# Chanel.net
KiCad netlist of a schematic drawn in Altium Designer
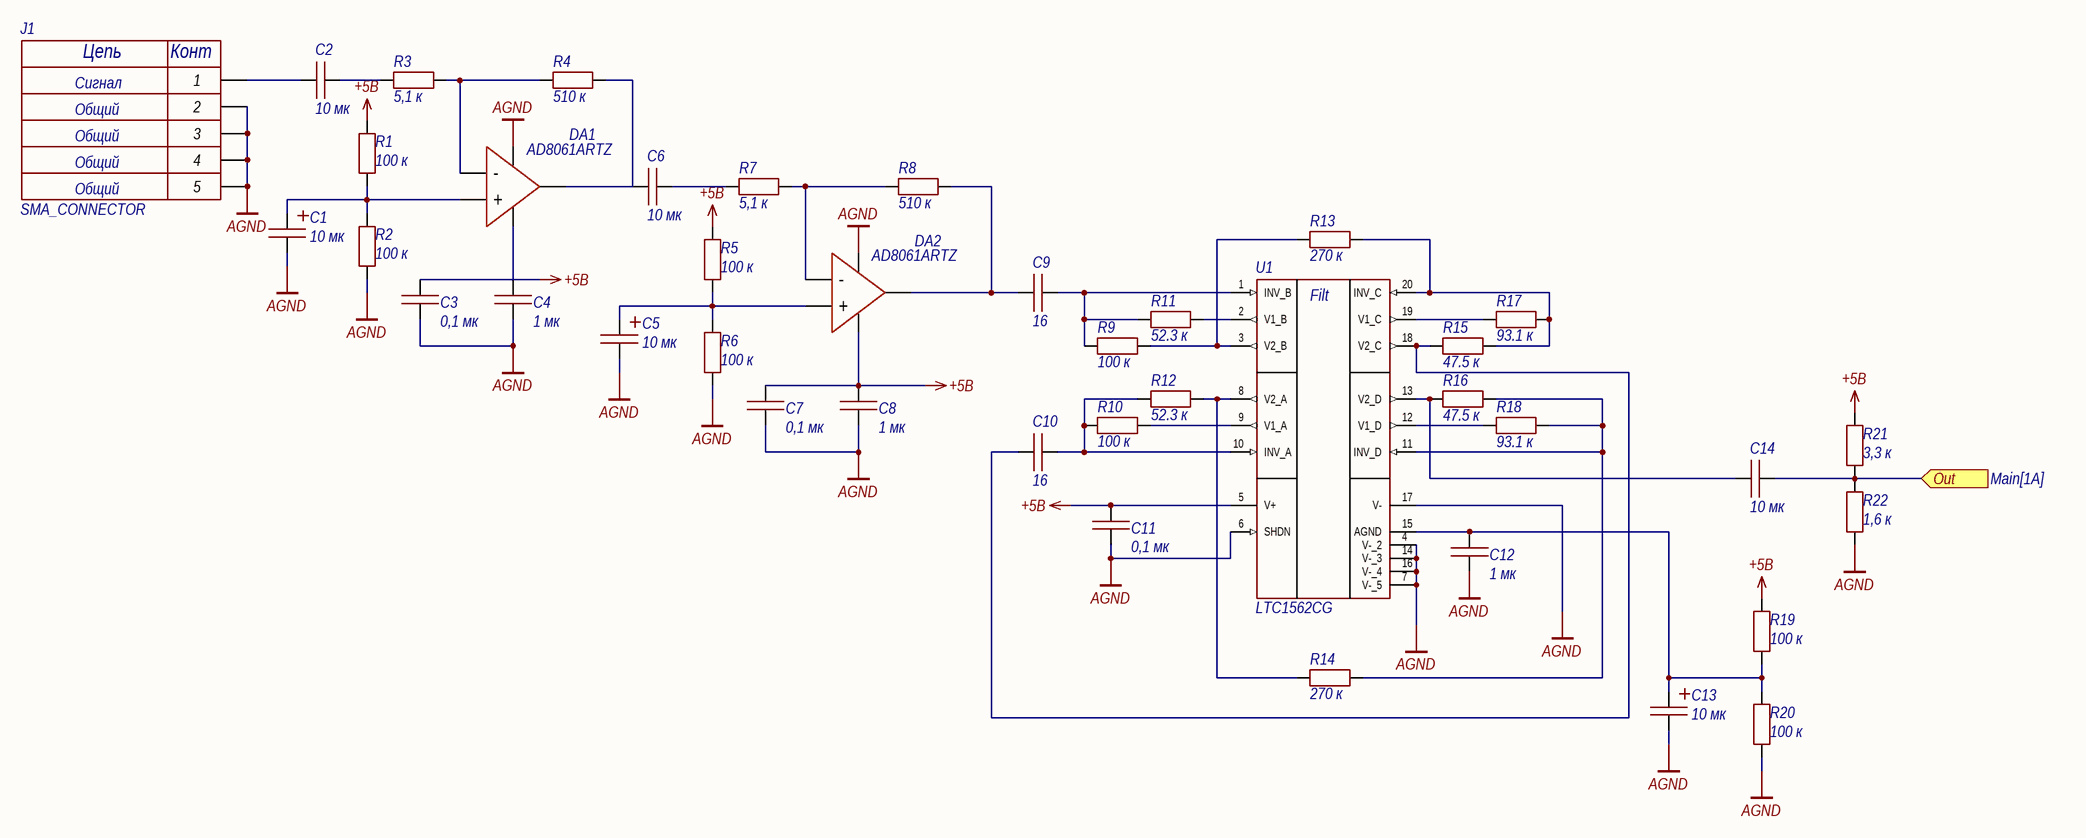
[diagram p0: Chanel.SchDoc]

(export (version "E")
  (design (tool "Eeschema 10.0.6"))
  (components
    (comp (ref "C1")
      (value "10 мк")
      (footprint "TC_A")
      (description "Танталовый конденсатор")
      (fields (field (name "PART NUMBER") "Capacitor_10u_10_50V_TC_A") (field (name "TOLERANCE") "0,1"))
      (libsource (lib "Hydrolib") (part "Capacitor_polar"))
    )
    (comp (ref "C2")
      (value "10 мк")
      (footprint "1210C")
      (description "Конденсатор 1210C ёмкостью 10 мк 10%, 35 В, X7R")
      (fields (field (name "PART NUMBER") "Capacitor_10u_10_35V_X7R_1210C") (field (name "TOLERANCE") "10%"))
      (libsource (lib "Hydrolib") (part "Capacitor"))
    )
    (comp (ref "C3")
      (value "0,1 мк")
      (footprint "0603C")
      (description "Конденсатор 0603C ёмкостью 0,1 мк 10%, 50 В, X7R")
      (fields (field (name "PART NUMBER") "Capacitor_0,1u_10_50V_X7R_0603C") (field (name "TOLERANCE") "10%"))
      (libsource (lib "Hydrolib") (part "Capacitor"))
    )
    (comp (ref "C4")
      (value "1 мк")
      (footprint "0603C")
      (description "Конденсатор 0603C ёмкостью 1 мк 10%, 50 В, X7R")
      (fields (field (name "PART NUMBER") "Capacitor_1u_10_50V_X7R_0603C") (field (name "TOLERANCE") "10%"))
      (libsource (lib "Hydrolib") (part "Capacitor"))
    )
    (comp (ref "C5")
      (value "10 мк")
      (footprint "TC_A")
      (description "Танталовый конденсатор")
      (fields (field (name "PART NUMBER") "Capacitor_10u_10_50V_TC_A") (field (name "TOLERANCE") "0,1"))
      (libsource (lib "Hydrolib") (part "Capacitor_polar"))
    )
    (comp (ref "C6")
      (value "10 мк")
      (footprint "1210C")
      (description "Конденсатор 1210C ёмкостью 10 мк 10%, 35 В, X7R")
      (fields (field (name "PART NUMBER") "Capacitor_10u_10_35V_X7R_1210C") (field (name "TOLERANCE") "10%"))
      (libsource (lib "Hydrolib") (part "Capacitor"))
    )
    (comp (ref "C7")
      (value "0,1 мк")
      (footprint "0603C")
      (description "Конденсатор 0603C ёмкостью 0,1 мк 10%, 50 В, X7R")
      (fields (field (name "PART NUMBER") "Capacitor_0,1u_10_50V_X7R_0603C") (field (name "TOLERANCE") "10%"))
      (libsource (lib "Hydrolib") (part "Capacitor"))
    )
    (comp (ref "C8")
      (value "1 мк")
      (footprint "0603C")
      (description "Конденсатор 0603C ёмкостью 1 мк 10%, 50 В, X7R")
      (fields (field (name "PART NUMBER") "Capacitor_1u_10_50V_X7R_0603C") (field (name "TOLERANCE") "10%"))
      (libsource (lib "Hydrolib") (part "Capacitor"))
    )
    (comp (ref "C9")
      (value "16")
      (footprint "0603C")
      (description "Конденсатор 0603C ёмкостью 1 н 10%, 50 В, X7R")
      (fields (field (name "PART NUMBER") "Capacitor_1n_10_50V_X7R_0603C") (field (name "TOLERANCE") "10%"))
      (libsource (lib "Hydrolib") (part "Capacitor"))
    )
    (comp (ref "C10")
      (value "16")
      (footprint "0603C")
      (description "Конденсатор 0603C ёмкостью 1 н 10%, 50 В, X7R")
      (fields (field (name "PART NUMBER") "Capacitor_1n_10_50V_X7R_0603C") (field (name "TOLERANCE") "10%"))
      (libsource (lib "Hydrolib") (part "Capacitor"))
    )
    (comp (ref "C11")
      (value "0,1 мк")
      (footprint "0603C")
      (description "Конденсатор 0603C ёмкостью 0,1 мк 10%, 50 В, X7R")
      (fields (field (name "PART NUMBER") "Capacitor_0,1u_10_50V_X7R_0603C") (field (name "TOLERANCE") "10%"))
      (libsource (lib "Hydrolib") (part "Capacitor"))
    )
    (comp (ref "C12")
      (value "1 мк")
      (footprint "0603C")
      (description "Конденсатор 0603C ёмкостью 1 мк 10%, 50 В, X7R")
      (fields (field (name "PART NUMBER") "Capacitor_1u_10_50V_X7R_0603C") (field (name "TOLERANCE") "10%"))
      (libsource (lib "Hydrolib") (part "Capacitor"))
    )
    (comp (ref "C13")
      (value "10 мк")
      (footprint "TC_A")
      (description "Танталовый конденсатор")
      (fields (field (name "PART NUMBER") "Capacitor_10u_10_50V_TC_A") (field (name "TOLERANCE") "0,1"))
      (libsource (lib "Hydrolib") (part "Capacitor_polar"))
    )
    (comp (ref "C14")
      (value "10 мк")
      (footprint "0603C")
      (description "Конденсатор 0603C ёмкостью 0,1 мк 10%, 50 В, X7R")
      (fields (field (name "PART NUMBER") "Capacitor_0,1u_10_50V_X7R_0603C") (field (name "TOLERANCE") "10%"))
      (libsource (lib "Hydrolib") (part "Capacitor"))
    )
    (comp (ref "DA1")
      (value "AD8061ARTZ")
      (footprint "SOT23-5")
      (description "Операционный усилитель Rail-to-Rail, 1-канальный")
      (fields (field (name "PART NUMBER") "TS951ILT") (field (name "АВТОР") "glebmih"))
      (libsource (lib "Hydrolib") (part "TS951ILT"))
    )
    (comp (ref "DA2")
      (value "AD8061ARTZ")
      (footprint "SOT23-5")
      (description "Операционный усилитель Rail-to-Rail, 1-канальный")
      (fields (field (name "PART NUMBER") "TS951ILT") (field (name "АВТОР") "glebmih"))
      (libsource (lib "Hydrolib") (part "TS951ILT"))
    )
    (comp (ref "J1")
      (value "SMA_CONNECTOR")
      (footprint "SMA_CONNECTOR")
      (description "Straight SMA Connector")
      (fields (field (name "MP") "altium_native_batch"))
      (libsource (lib "Hydrolib") (part "SMA_CONNECTOR"))
    )
    (comp (ref "R1")
      (value "100 к")
      (footprint "0603R")
      (description "Резистор номиналом 100 кОм 1%")
      (fields (field (name "PART NUMBER") "Resistor_100k_1_0603") (field (name "TOLERANCE") "1%"))
      (libsource (lib "Hydrolib") (part "Resistor"))
    )
    (comp (ref "R2")
      (value "100 к")
      (footprint "0603R")
      (description "Резистор номиналом 100 кОм 1%")
      (fields (field (name "PART NUMBER") "Resistor_100k_1_0603") (field (name "TOLERANCE") "1%"))
      (libsource (lib "Hydrolib") (part "Resistor"))
    )
    (comp (ref "R3")
      (value "5,1 к")
      (footprint "0603R")
      (description "Резистор номиналом 100 кОм 1%")
      (fields (field (name "PART NUMBER") "Resistor_100k_1_0603") (field (name "TOLERANCE") "1%"))
      (libsource (lib "") (part "Resistor_2"))
    )
    (comp (ref "R4")
      (value "510 к")
      (footprint "0603R")
      (description "Резистор номиналом 510 кОм 1%")
      (fields (field (name "PART NUMBER") "Resistor_510k_1_0603") (field (name "TOLERANCE") "1%"))
      (libsource (lib "") (part "Resistor_1"))
    )
    (comp (ref "R5")
      (value "100 к")
      (footprint "0603R")
      (description "Резистор номиналом 100 кОм 1%")
      (fields (field (name "PART NUMBER") "Resistor_100k_1_0603") (field (name "TOLERANCE") "1%"))
      (libsource (lib "Hydrolib") (part "Resistor"))
    )
    (comp (ref "R6")
      (value "100 к")
      (footprint "0603R")
      (description "Резистор номиналом 100 кОм 1%")
      (fields (field (name "PART NUMBER") "Resistor_100k_1_0603") (field (name "TOLERANCE") "1%"))
      (libsource (lib "Hydrolib") (part "Resistor"))
    )
    (comp (ref "R7")
      (value "5,1 к")
      (footprint "0603R")
      (description "Резистор номиналом 100 кОм 1%")
      (fields (field (name "PART NUMBER") "Resistor_100k_1_0603") (field (name "TOLERANCE") "1%"))
      (libsource (lib "") (part "Resistor_2"))
    )
    (comp (ref "R8")
      (value "510 к")
      (footprint "0603R")
      (description "Резистор номиналом 510 кОм 1%")
      (fields (field (name "PART NUMBER") "Resistor_510k_1_0603") (field (name "TOLERANCE") "1%"))
      (libsource (lib "") (part "Resistor_1"))
    )
    (comp (ref "R9")
      (value "100 к")
      (footprint "0603R")
      (description "Резистор номиналом 51 кОм 1%")
      (fields (field (name "PART NUMBER") "Resistor_51k_1_0603") (field (name "TOLERANCE") "1%"))
      (libsource (lib "") (part "Resistor_1"))
    )
    (comp (ref "R10")
      (value "100 к")
      (footprint "0603R")
      (description "Резистор номиналом 51 кОм 1%")
      (fields (field (name "PART NUMBER") "Resistor_51k_1_0603") (field (name "TOLERANCE") "1%"))
      (libsource (lib "") (part "Resistor_1"))
    )
    (comp (ref "R11")
      (value "52.3 к")
      (footprint "0603R")
      (description "Резистор номиналом 51 кОм 1%")
      (fields (field (name "PART NUMBER") "Resistor_51k_1_0603") (field (name "TOLERANCE") "1%"))
      (libsource (lib "") (part "Resistor_1"))
    )
    (comp (ref "R12")
      (value "52.3 к")
      (footprint "0603R")
      (description "Резистор номиналом 51 кОм 1%")
      (fields (field (name "PART NUMBER") "Resistor_51k_1_0603") (field (name "TOLERANCE") "1%"))
      (libsource (lib "") (part "Resistor_1"))
    )
    (comp (ref "R13")
      (value "270 к")
      (footprint "0603R")
      (description "Резистор номиналом 51 кОм 1%")
      (fields (field (name "PART NUMBER") "Resistor_51k_1_0603") (field (name "TOLERANCE") "1%"))
      (libsource (lib "") (part "Resistor_1"))
    )
    (comp (ref "R14")
      (value "270 к")
      (footprint "0603R")
      (description "Резистор номиналом 51 кОм 1%")
      (fields (field (name "PART NUMBER") "Resistor_51k_1_0603") (field (name "TOLERANCE") "1%"))
      (libsource (lib "") (part "Resistor_1"))
    )
    (comp (ref "R15")
      (value "47.5 к")
      (footprint "0603R")
      (description "Резистор номиналом 47 кОм 1%")
      (fields (field (name "PART NUMBER") "Resistor_47k_1_0603") (field (name "TOLERANCE") "1%"))
      (libsource (lib "") (part "Resistor_1"))
    )
    (comp (ref "R16")
      (value "47.5 к")
      (footprint "0603R")
      (description "Резистор номиналом 47 кОм 1%")
      (fields (field (name "PART NUMBER") "Resistor_47k_1_0603") (field (name "TOLERANCE") "1%"))
      (libsource (lib "") (part "Resistor_1"))
    )
    (comp (ref "R17")
      (value "93.1 к")
      (footprint "0603R")
      (description "Резистор номиналом 91 кОм 1%")
      (fields (field (name "PART NUMBER") "Resistor_91k_1_0603") (field (name "TOLERANCE") "1%"))
      (libsource (lib "") (part "Resistor_1"))
    )
    (comp (ref "R18")
      (value "93.1 к")
      (footprint "0603R")
      (description "Резистор номиналом 91 кОм 1%")
      (fields (field (name "PART NUMBER") "Resistor_91k_1_0603") (field (name "TOLERANCE") "1%"))
      (libsource (lib "") (part "Resistor_1"))
    )
    (comp (ref "R19")
      (value "100 к")
      (footprint "0603R")
      (description "Резистор номиналом 100 кОм 1%")
      (fields (field (name "PART NUMBER") "Resistor_100k_1_0603") (field (name "TOLERANCE") "1%"))
      (libsource (lib "Hydrolib") (part "Resistor"))
    )
    (comp (ref "R20")
      (value "100 к")
      (footprint "0603R")
      (description "Резистор номиналом 100 кОм 1%")
      (fields (field (name "PART NUMBER") "Resistor_100k_1_0603") (field (name "TOLERANCE") "1%"))
      (libsource (lib "Hydrolib") (part "Resistor"))
    )
    (comp (ref "R21")
      (value "3,3 к")
      (footprint "0603R")
      (description "Резистор номиналом 3,3 кОм 1%")
      (fields (field (name "PART NUMBER") "Resistor_3.3k_1_0603") (field (name "TOLERANCE") "1%"))
      (libsource (lib "Hydrolib") (part "Resistor"))
    )
    (comp (ref "R22")
      (value "1,6 к")
      (footprint "0603R")
      (description "Резистор номиналом 1,6 кОм 1%")
      (fields (field (name "PART NUMBER") "Resistor_1.6k_1_0603") (field (name "TOLERANCE") "1%"))
      (libsource (lib "Hydrolib") (part "Resistor"))
    )
    (comp (ref "U1")
      (value "LTC1562CG")
      (footprint "20-SSOP")
      (description "Микросхема счетверённый активный полосовый фильтр")
      (fields (field (name "MF") "Analog Devices") (field (name "MP") "LTC1562CG#TR"))
      (libsource (lib "Hydrolib") (part "LTC1562CG"))
    )
  )
  (nets
    (net (code "1") (name "+5В") (class "Default")
      (node (ref "C11") (pin "2") (pinfunction "2_2") (pintype "passive"))
      (node (ref "C3") (pin "2") (pinfunction "2_2") (pintype "passive"))
      (node (ref "C4") (pin "2") (pinfunction "2_2") (pintype "passive"))
      (node (ref "C7") (pin "2") (pinfunction "2_2") (pintype "passive"))
      (node (ref "C8") (pin "2") (pinfunction "2_2") (pintype "passive"))
      (node (ref "DA1") (pin "5") (pinfunction "VCC_5") (pintype "passive"))
      (node (ref "DA2") (pin "5") (pinfunction "VCC_5") (pintype "passive"))
      (node (ref "R1") (pin "2") (pinfunction "2_2") (pintype "passive"))
      (node (ref "R19") (pin "2") (pinfunction "2_2") (pintype "passive"))
      (node (ref "R21") (pin "2") (pinfunction "2_2") (pintype "passive"))
      (node (ref "R5") (pin "2") (pinfunction "2_2") (pintype "passive"))
      (node (ref "U1") (pin "5") (pinfunction "V+_5") (pintype "power_in"))
    )
    (net (code "2") (name "/Out") (class "Default")
      (node (ref "C14") (pin "2") (pinfunction "2_2") (pintype "passive"))
      (node (ref "R21") (pin "1") (pinfunction "1_1") (pintype "passive"))
      (node (ref "R22") (pin "2") (pinfunction "2_2") (pintype "passive"))
    )
    (net (code "3") (name "AGND") (class "Default")
      (node (ref "C1") (pin "2") (pinfunction "2_2") (pintype "passive"))
      (node (ref "C11") (pin "1") (pinfunction "1_1") (pintype "passive"))
      (node (ref "C12") (pin "1") (pinfunction "1_1") (pintype "passive"))
      (node (ref "C13") (pin "2") (pinfunction "2_2") (pintype "passive"))
      (node (ref "C3") (pin "1") (pinfunction "1_1") (pintype "passive"))
      (node (ref "C4") (pin "1") (pinfunction "1_1") (pintype "passive"))
      (node (ref "C5") (pin "2") (pinfunction "2_2") (pintype "passive"))
      (node (ref "C7") (pin "1") (pinfunction "1_1") (pintype "passive"))
      (node (ref "C8") (pin "1") (pinfunction "1_1") (pintype "passive"))
      (node (ref "DA1") (pin "2") (pinfunction "GND_2") (pintype "passive"))
      (node (ref "DA2") (pin "2") (pinfunction "GND_2") (pintype "passive"))
      (node (ref "J1") (pin "G1") (pinfunction "2_G1") (pintype "passive"))
      (node (ref "J1") (pin "G2") (pinfunction "3_G2") (pintype "passive"))
      (node (ref "J1") (pin "G3") (pinfunction "4_G3") (pintype "passive"))
      (node (ref "J1") (pin "G4") (pinfunction "5_G4") (pintype "passive"))
      (node (ref "R2") (pin "1") (pinfunction "1_1") (pintype "passive"))
      (node (ref "R20") (pin "1") (pinfunction "1_1") (pintype "passive"))
      (node (ref "R22") (pin "1") (pinfunction "1_1") (pintype "passive"))
      (node (ref "R6") (pin "1") (pinfunction "1_1") (pintype "passive"))
      (node (ref "U1") (pin "14") (pinfunction "V-_3_14") (pintype "power_in"))
      (node (ref "U1") (pin "16") (pinfunction "V-_4_16") (pintype "power_in"))
      (node (ref "U1") (pin "17") (pinfunction "V-_17") (pintype "power_in"))
      (node (ref "U1") (pin "4") (pinfunction "V-_2_4") (pintype "power_in"))
      (node (ref "U1") (pin "6") (pinfunction "SHDN_6") (pintype "input"))
      (node (ref "U1") (pin "7") (pinfunction "V-_5_7") (pintype "power_in"))
    )
    (net (code "4") (name "Net-(C2-Pad1)") (class "Default")
      (node (ref "C2") (pin "1") (pinfunction "1_1") (pintype "passive"))
      (node (ref "J1") (pin "1") (pinfunction "1_1") (pintype "passive"))
    )
    (net (code "5") (name "Net-(C2-Pad2)") (class "Default")
      (node (ref "C2") (pin "2") (pinfunction "2_2") (pintype "passive"))
      (node (ref "R3") (pin "2") (pinfunction "2_2") (pintype "passive"))
    )
    (net (code "6") (name "Net-(C6-Pad1)") (class "Default")
      (node (ref "C6") (pin "1") (pinfunction "1_1") (pintype "passive"))
      (node (ref "DA1") (pin "1") (pintype "passive"))
      (node (ref "R4") (pin "2") (pinfunction "2_2") (pintype "passive"))
    )
    (net (code "7") (name "Net-(C6-Pad2)") (class "Default")
      (node (ref "C6") (pin "2") (pinfunction "2_2") (pintype "passive"))
      (node (ref "R7") (pin "2") (pinfunction "2_2") (pintype "passive"))
    )
    (net (code "8") (name "Net-(C9-Pad1)") (class "Default")
      (node (ref "C9") (pin "1") (pinfunction "1_1") (pintype "passive"))
      (node (ref "DA2") (pin "1") (pintype "passive"))
      (node (ref "R8") (pin "2") (pinfunction "2_2") (pintype "passive"))
    )
    (net (code "9") (name "Net-(DA1-+)") (class "Default")
      (node (ref "C1") (pin "1") (pinfunction "1_1") (pintype "passive"))
      (node (ref "DA1") (pin "3") (pinfunction "+_3") (pintype "passive"))
      (node (ref "R1") (pin "1") (pinfunction "1_1") (pintype "passive"))
      (node (ref "R2") (pin "2") (pinfunction "2_2") (pintype "passive"))
    )
    (net (code "10") (name "Net-(DA1--)") (class "Default")
      (node (ref "DA1") (pin "4") (pinfunction "-_4") (pintype "passive"))
      (node (ref "R3") (pin "1") (pinfunction "1_1") (pintype "passive"))
      (node (ref "R4") (pin "1") (pinfunction "1_1") (pintype "passive"))
    )
    (net (code "11") (name "Net-(DA2-+)") (class "Default")
      (node (ref "C5") (pin "1") (pinfunction "1_1") (pintype "passive"))
      (node (ref "DA2") (pin "3") (pinfunction "+_3") (pintype "passive"))
      (node (ref "R5") (pin "1") (pinfunction "1_1") (pintype "passive"))
      (node (ref "R6") (pin "2") (pinfunction "2_2") (pintype "passive"))
    )
    (net (code "12") (name "Net-(DA2--)") (class "Default")
      (node (ref "DA2") (pin "4") (pinfunction "-_4") (pintype "passive"))
      (node (ref "R7") (pin "1") (pinfunction "1_1") (pintype "passive"))
      (node (ref "R8") (pin "1") (pinfunction "1_1") (pintype "passive"))
    )
    (net (code "13") (name "Net-(U1-AGND)") (class "Default")
      (node (ref "C12") (pin "2") (pinfunction "2_2") (pintype "passive"))
      (node (ref "C13") (pin "1") (pinfunction "1_1") (pintype "passive"))
      (node (ref "R19") (pin "1") (pinfunction "1_1") (pintype "passive"))
      (node (ref "R20") (pin "2") (pinfunction "2_2") (pintype "passive"))
      (node (ref "U1") (pin "15") (pinfunction "AGND_15") (pintype "passive"))
    )
    (net (code "14") (name "Net-(U1-INV_A)") (class "Default")
      (node (ref "C10") (pin "2") (pinfunction "2_2") (pintype "passive"))
      (node (ref "R10") (pin "1") (pinfunction "1_1") (pintype "passive"))
      (node (ref "R12") (pin "1") (pinfunction "1_1") (pintype "passive"))
      (node (ref "U1") (pin "10") (pinfunction "INV_A_10") (pintype "input"))
    )
    (net (code "15") (name "Net-(U1-INV_B)") (class "Default")
      (node (ref "C9") (pin "2") (pinfunction "2_2") (pintype "passive"))
      (node (ref "R11") (pin "1") (pinfunction "1_1") (pintype "passive"))
      (node (ref "R9") (pin "1") (pinfunction "1_1") (pintype "passive"))
      (node (ref "U1") (pin "1") (pinfunction "INV_B_1") (pintype "input"))
    )
    (net (code "16") (name "Net-(U1-INV_C)") (class "Default")
      (node (ref "R13") (pin "2") (pinfunction "2_2") (pintype "passive"))
      (node (ref "R15") (pin "2") (pinfunction "2_2") (pintype "passive"))
      (node (ref "R17") (pin "2") (pinfunction "2_2") (pintype "passive"))
      (node (ref "U1") (pin "20") (pinfunction "INV_C_20") (pintype "input"))
    )
    (net (code "17") (name "Net-(U1-INV_D)") (class "Default")
      (node (ref "R14") (pin "2") (pinfunction "2_2") (pintype "passive"))
      (node (ref "R16") (pin "2") (pinfunction "2_2") (pintype "passive"))
      (node (ref "R18") (pin "2") (pinfunction "2_2") (pintype "passive"))
      (node (ref "U1") (pin "11") (pinfunction "INV_D_11") (pintype "input"))
    )
    (net (code "18") (name "Net-(U1-V1_A)") (class "Default")
      (node (ref "R10") (pin "2") (pinfunction "2_2") (pintype "passive"))
      (node (ref "U1") (pin "9") (pinfunction "V1_A_9") (pintype "output"))
    )
    (net (code "19") (name "Net-(U1-V1_B)") (class "Default")
      (node (ref "R11") (pin "2") (pinfunction "2_2") (pintype "passive"))
      (node (ref "U1") (pin "2") (pinfunction "V1_B_2") (pintype "output"))
    )
    (net (code "20") (name "Net-(U1-V1_C)") (class "Default")
      (node (ref "R17") (pin "1") (pinfunction "1_1") (pintype "passive"))
      (node (ref "U1") (pin "19") (pinfunction "V1_C_19") (pintype "output"))
    )
    (net (code "21") (name "Net-(U1-V1_D)") (class "Default")
      (node (ref "R18") (pin "1") (pinfunction "1_1") (pintype "passive"))
      (node (ref "U1") (pin "12") (pinfunction "V1_D_12") (pintype "output"))
    )
    (net (code "22") (name "Net-(U1-V2_A)") (class "Default")
      (node (ref "R12") (pin "2") (pinfunction "2_2") (pintype "passive"))
      (node (ref "R14") (pin "1") (pinfunction "1_1") (pintype "passive"))
      (node (ref "U1") (pin "8") (pinfunction "V2_A_8") (pintype "output"))
    )
    (net (code "23") (name "Net-(U1-V2_B)") (class "Default")
      (node (ref "R13") (pin "1") (pinfunction "1_1") (pintype "passive"))
      (node (ref "R9") (pin "2") (pinfunction "2_2") (pintype "passive"))
      (node (ref "U1") (pin "3") (pinfunction "V2_B_3") (pintype "output"))
    )
    (net (code "24") (name "Net-(U1-V2_C)") (class "Default")
      (node (ref "C10") (pin "1") (pinfunction "1_1") (pintype "passive"))
      (node (ref "R15") (pin "1") (pinfunction "1_1") (pintype "passive"))
      (node (ref "U1") (pin "18") (pinfunction "V2_C_18") (pintype "output"))
    )
    (net (code "25") (name "Net-(U1-V2_D)") (class "Default")
      (node (ref "C14") (pin "1") (pinfunction "1_1") (pintype "passive"))
      (node (ref "R16") (pin "1") (pinfunction "1_1") (pintype "passive"))
      (node (ref "U1") (pin "13") (pinfunction "V2_D_13") (pintype "output"))
    )
  )
)
